# pcb1.net
KiCad netlist of a schematic drawn in Altium Designer
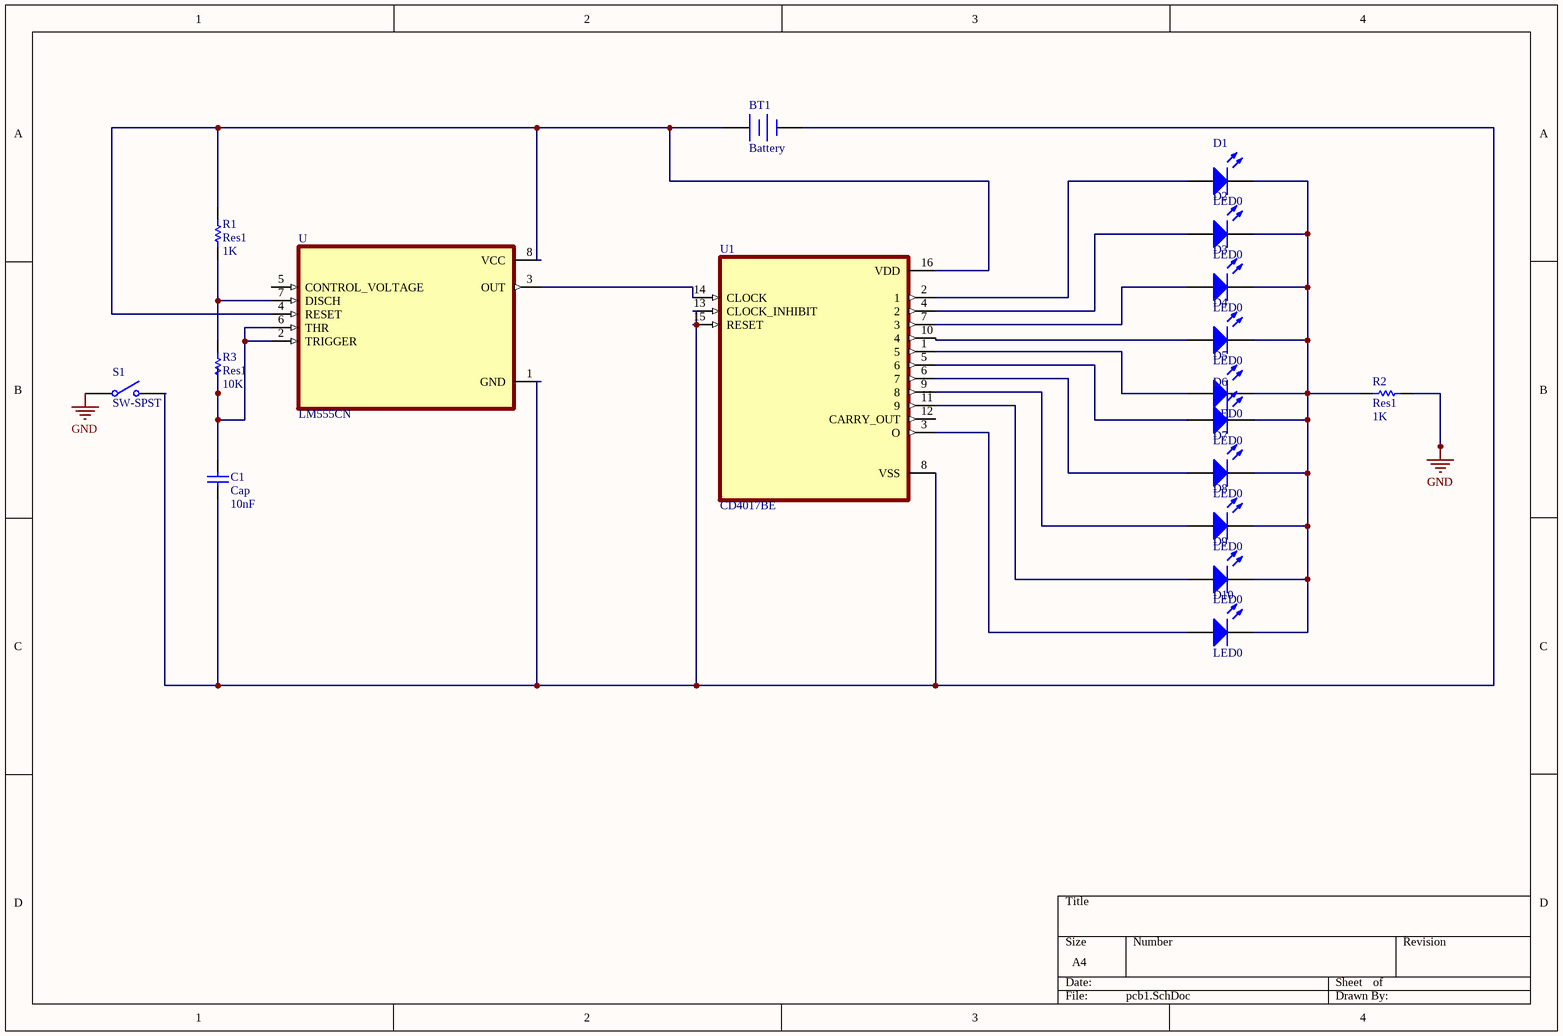
[diagram p0: pcb1.SchDoc]

(export (version "E")
  (design (tool "Eeschema 10.0.6"))
  (components
    (comp (ref "BT1")
      (value "Battery")
      (footprint "BAT-2")
      (description "Multicell Battery")
      (fields (field (name "PUBLISHER") "Altium Limited"))
      (libsource (lib "Miscellaneous Devices") (part "Battery"))
    )
    (comp (ref "C1")
      (value "Cap")
      (footprint "RAD-0.3")
      (description "Capacitor")
      (fields (field (name "ALTIUM_VALUE") "10nF") (field (name "PUBLISHER") "Altium Limited"))
      (libsource (lib "Miscellaneous Devices") (part "Cap"))
    )
    (comp (ref "D1")
      (value "LED0")
      (footprint "LED-0")
      (description "Typical INFRARED GaAs LED")
      (fields (field (name "PUBLISHER") "Altium Limited"))
      (libsource (lib "Miscellaneous Devices") (part "LED0"))
    )
    (comp (ref "D2")
      (value "LED0")
      (footprint "LED-0")
      (description "Typical INFRARED GaAs LED")
      (fields (field (name "PUBLISHER") "Altium Limited"))
      (libsource (lib "Miscellaneous Devices") (part "LED0"))
    )
    (comp (ref "D3")
      (value "LED0")
      (footprint "LED-0")
      (description "Typical INFRARED GaAs LED")
      (fields (field (name "PUBLISHER") "Altium Limited"))
      (libsource (lib "Miscellaneous Devices") (part "LED0"))
    )
    (comp (ref "D4")
      (value "LED0")
      (footprint "LED-0")
      (description "Typical INFRARED GaAs LED")
      (fields (field (name "PUBLISHER") "Altium Limited"))
      (libsource (lib "Miscellaneous Devices") (part "LED0"))
    )
    (comp (ref "D5")
      (value "LED0")
      (footprint "LED-0")
      (description "Typical INFRARED GaAs LED")
      (fields (field (name "PUBLISHER") "Altium Limited"))
      (libsource (lib "Miscellaneous Devices") (part "LED0"))
    )
    (comp (ref "D6")
      (value "LED0")
      (footprint "LED-0")
      (description "Typical INFRARED GaAs LED")
      (fields (field (name "PUBLISHER") "Altium Limited"))
      (libsource (lib "Miscellaneous Devices") (part "LED0"))
    )
    (comp (ref "D7")
      (value "LED0")
      (footprint "LED-0")
      (description "Typical INFRARED GaAs LED")
      (fields (field (name "PUBLISHER") "Altium Limited"))
      (libsource (lib "Miscellaneous Devices") (part "LED0"))
    )
    (comp (ref "D8")
      (value "LED0")
      (footprint "LED-0")
      (description "Typical INFRARED GaAs LED")
      (fields (field (name "PUBLISHER") "Altium Limited"))
      (libsource (lib "Miscellaneous Devices") (part "LED0"))
    )
    (comp (ref "D9")
      (value "LED0")
      (footprint "LED-0")
      (description "Typical INFRARED GaAs LED")
      (fields (field (name "PUBLISHER") "Altium Limited"))
      (libsource (lib "Miscellaneous Devices") (part "LED0"))
    )
    (comp (ref "D10")
      (value "LED0")
      (footprint "LED-0")
      (description "Typical INFRARED GaAs LED")
      (fields (field (name "PUBLISHER") "Altium Limited"))
      (libsource (lib "Miscellaneous Devices") (part "LED0"))
    )
    (comp (ref "R1")
      (value "Res1")
      (footprint "AXIAL-0.3")
      (description "Resistor")
      (fields (field (name "ALTIUM_VALUE") "1K") (field (name "PUBLISHER") "Altium Limited"))
      (libsource (lib "Miscellaneous Devices") (part "Res1"))
    )
    (comp (ref "R2")
      (value "Res1")
      (footprint "AXIAL-0.3")
      (description "Resistor")
      (fields (field (name "ALTIUM_VALUE") "1K") (field (name "PUBLISHER") "Altium Limited"))
      (libsource (lib "Miscellaneous Devices") (part "Res1"))
    )
    (comp (ref "R3")
      (value "Res1")
      (footprint "AXIAL-0.3")
      (description "Resistor")
      (fields (field (name "ALTIUM_VALUE") "10K") (field (name "PUBLISHER") "Altium Limited"))
      (libsource (lib "Miscellaneous Devices") (part "Res1"))
    )
    (comp (ref "S1")
      (value "SW-SPST")
      (footprint "SPST-2")
      (description "Single-Pole, Single-Throw Switch")
      (fields (field (name "PUBLISHER") "Altium Limited"))
      (libsource (lib "Miscellaneous Devices") (part "SW-SPST"))
    )
    (comp (ref "U")
      (value "LM555CN")
      (footprint "DIP762W46P254L960H508Q8")
      (description "555 Type, Timer/Oscillator (Single) IC 100kHz 8-PDIP")
      (fields (field (name "MF") "Texas Instruments"))
      (libsource (lib "LM555CN") (part "LM555CN"))
    )
    (comp (ref "U1")
      (value "CD4017BE")
      (footprint "DIP794W45P254L1969H508Q16")
      (description "CMOS Decade Counter with 10 Decoded Outputs")
      (fields (field (name "MF") "Texas Instruments"))
      (libsource (lib "CD4017BE") (part "CD4017BE"))
    )
  )
  (nets
    (net (code "1") (name "GND") (class "Default")
      (node (ref "R2") (pin "1") (pinfunction "1_1") (pintype "passive"))
      (node (ref "S1") (pin "1") (pinfunction "COMMON_1") (pintype "passive"))
    )
    (net (code "2") (name "Net-(BT1-+)") (class "Default")
      (node (ref "BT1") (pin "1") (pinfunction "+_1") (pintype "passive"))
      (node (ref "R1") (pin "2") (pinfunction "2_2") (pintype "passive"))
      (node (ref "U") (pin "4") (pinfunction "RESET_4") (pintype "input"))
      (node (ref "U") (pin "8") (pinfunction "VCC_8") (pintype "power_in"))
      (node (ref "U1") (pin "16") (pinfunction "VDD_16") (pintype "power_in"))
    )
    (net (code "3") (name "Net-(BT1--)") (class "Default")
      (node (ref "BT1") (pin "2") (pinfunction "-_2") (pintype "passive"))
      (node (ref "C1") (pin "1") (pinfunction "1_1") (pintype "passive"))
      (node (ref "S1") (pin "2") (pinfunction "NO_2") (pintype "passive"))
      (node (ref "U") (pin "1") (pinfunction "GND_1") (pintype "power_in"))
      (node (ref "U1") (pin "13") (pinfunction "CLOCK_INHIBIT_13") (pintype "input"))
      (node (ref "U1") (pin "15") (pinfunction "RESET_15") (pintype "input"))
      (node (ref "U1") (pin "8") (pinfunction "VSS_8") (pintype "power_in"))
    )
    (net (code "4") (name "Net-(D1-A)") (class "Default")
      (node (ref "D1") (pin "1") (pinfunction "A_1") (pintype "passive"))
      (node (ref "U1") (pin "2") (pinfunction "1_2") (pintype "output"))
    )
    (net (code "5") (name "Net-(D1-K)") (class "Default")
      (node (ref "D1") (pin "2") (pinfunction "K_2") (pintype "passive"))
      (node (ref "D10") (pin "2") (pinfunction "K_2") (pintype "passive"))
      (node (ref "D2") (pin "2") (pinfunction "K_2") (pintype "passive"))
      (node (ref "D3") (pin "2") (pinfunction "K_2") (pintype "passive"))
      (node (ref "D4") (pin "2") (pinfunction "K_2") (pintype "passive"))
      (node (ref "D5") (pin "2") (pinfunction "K_2") (pintype "passive"))
      (node (ref "D6") (pin "2") (pinfunction "K_2") (pintype "passive"))
      (node (ref "D7") (pin "2") (pinfunction "K_2") (pintype "passive"))
      (node (ref "D8") (pin "2") (pinfunction "K_2") (pintype "passive"))
      (node (ref "D9") (pin "2") (pinfunction "K_2") (pintype "passive"))
      (node (ref "R2") (pin "2") (pinfunction "2_2") (pintype "passive"))
    )
    (net (code "6") (name "Net-(D2-A)") (class "Default")
      (node (ref "D2") (pin "1") (pinfunction "A_1") (pintype "passive"))
      (node (ref "U1") (pin "4") (pinfunction "2_4") (pintype "output"))
    )
    (net (code "7") (name "Net-(D3-A)") (class "Default")
      (node (ref "D3") (pin "1") (pinfunction "A_1") (pintype "passive"))
      (node (ref "U1") (pin "7") (pinfunction "3_7") (pintype "output"))
    )
    (net (code "8") (name "Net-(D4-A)") (class "Default")
      (node (ref "D4") (pin "1") (pinfunction "A_1") (pintype "passive"))
      (node (ref "U1") (pin "10") (pinfunction "4_10") (pintype "output"))
    )
    (net (code "9") (name "Net-(D5-A)") (class "Default")
      (node (ref "D5") (pin "1") (pinfunction "A_1") (pintype "passive"))
      (node (ref "U1") (pin "1") (pinfunction "5_1") (pintype "output"))
    )
    (net (code "10") (name "Net-(D6-A)") (class "Default")
      (node (ref "D6") (pin "1") (pinfunction "A_1") (pintype "passive"))
      (node (ref "U1") (pin "5") (pinfunction "6_5") (pintype "output"))
    )
    (net (code "11") (name "Net-(D7-A)") (class "Default")
      (node (ref "D7") (pin "1") (pinfunction "A_1") (pintype "passive"))
      (node (ref "U1") (pin "6") (pinfunction "7_6") (pintype "output"))
    )
    (net (code "12") (name "Net-(D8-A)") (class "Default")
      (node (ref "D8") (pin "1") (pinfunction "A_1") (pintype "passive"))
      (node (ref "U1") (pin "9") (pinfunction "8_9") (pintype "output"))
    )
    (net (code "13") (name "Net-(D9-A)") (class "Default")
      (node (ref "D9") (pin "1") (pinfunction "A_1") (pintype "passive"))
      (node (ref "U1") (pin "11") (pinfunction "9_11") (pintype "output"))
    )
    (net (code "14") (name "Net-(D10-A)") (class "Default")
      (node (ref "D10") (pin "1") (pinfunction "A_1") (pintype "passive"))
      (node (ref "U1") (pin "3") (pinfunction "O_3") (pintype "output"))
    )
    (net (code "15") (name "Net-(U-DISCH)") (class "Default")
      (node (ref "R1") (pin "1") (pinfunction "1_1") (pintype "passive"))
      (node (ref "R3") (pin "2") (pinfunction "2_2") (pintype "passive"))
      (node (ref "U") (pin "7") (pinfunction "DISCH_7") (pintype "input"))
    )
    (net (code "16") (name "Net-(U-OUT)") (class "Default")
      (node (ref "U") (pin "3") (pinfunction "OUT_3") (pintype "output"))
      (node (ref "U1") (pin "14") (pinfunction "CLOCK_14") (pintype "input"))
    )
    (net (code "17") (name "Net-(U-THR)") (class "Default")
      (node (ref "C1") (pin "2") (pinfunction "2_2") (pintype "passive"))
      (node (ref "R3") (pin "1") (pinfunction "1_1") (pintype "passive"))
      (node (ref "U") (pin "2") (pinfunction "TRIGGER_2") (pintype "input"))
      (node (ref "U") (pin "6") (pinfunction "THR_6") (pintype "input"))
    )
    (net (code "18") (name "unconnected-(U-CONTROL_VOLTAGE-Pad5)") (class "Default")
      (node (ref "U") (pin "5") (pinfunction "CONTROL_VOLTAGE_5") (pintype "input"))
    )
    (net (code "19") (name "unconnected-(U1-CARRY_OUT-Pad12)") (class "Default")
      (node (ref "U1") (pin "12") (pinfunction "CARRY_OUT_12") (pintype "output"))
    )
  )
)
